# Control.net
KiCad netlist of a schematic drawn in Altium Designer
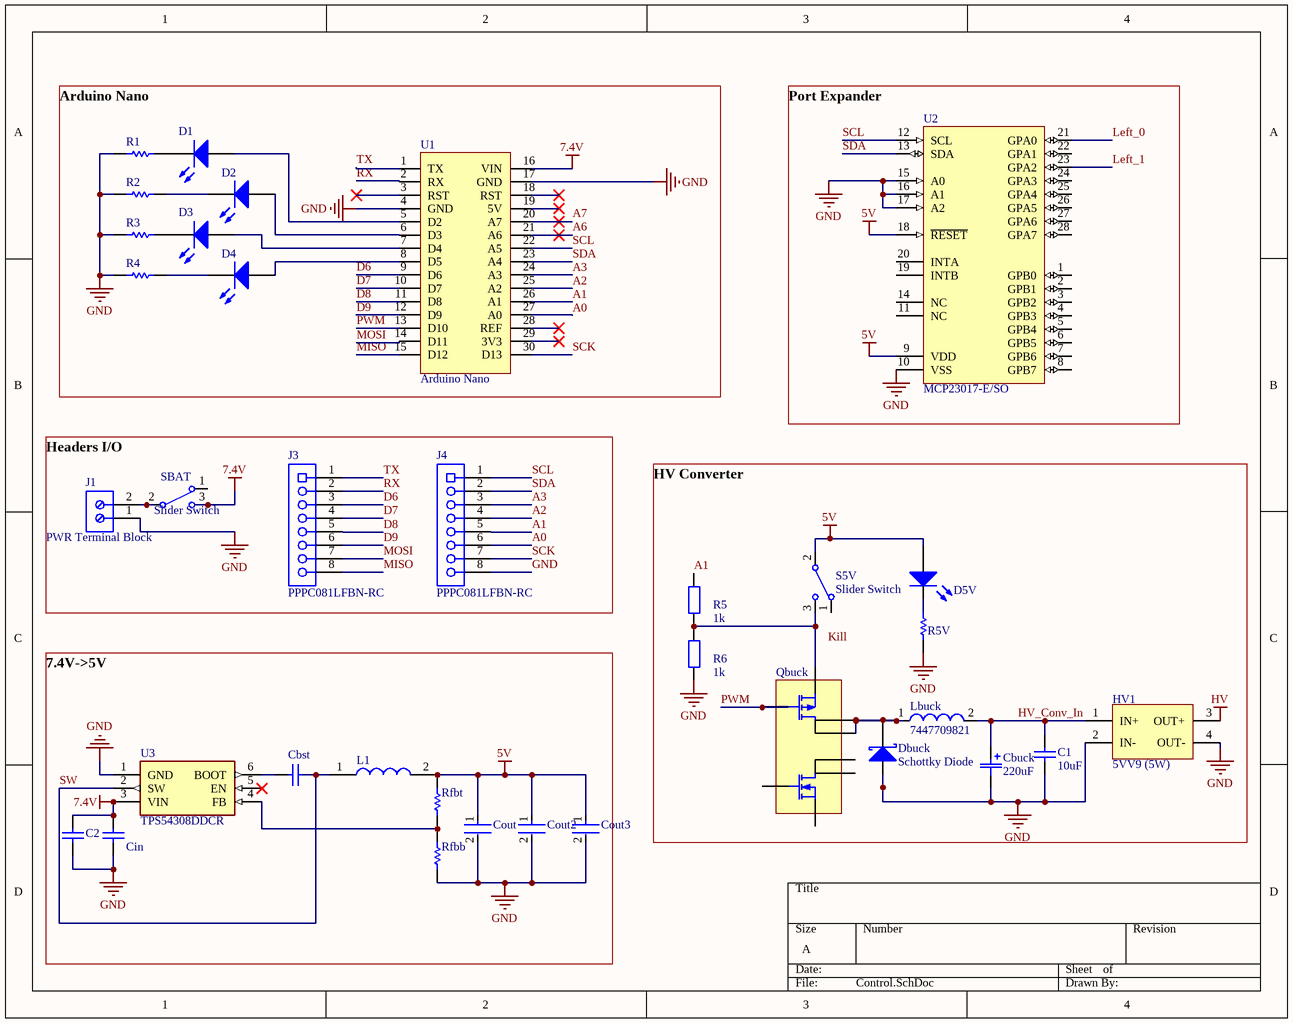
[diagram p0: Control.SchDoc]

(export (version "E")
  (design (tool "Eeschema 10.0.6"))
  (components
    (comp (ref "C1")
      (value "10uF")
      (footprint "1206 CAP")
      (description "1276-3038-6-ND\r\nManufacturer: CL31A106KAHNFNE")
      (fields (field (name "Comment") "Capacitor 10uF"))
      (libsource (lib "Schlib") (part "Capacitor 10uF"))
    )
    (comp (ref "C2")
      (value "C0805C104K5RACTU")
      (footprint "CAPC2013X88X50NL20T25")
      (fields (field (name "MANUFACTURER") "Kemet"))
      (libsource (lib "Altium Content Vault") (part "CAP"))
    )
    (comp (ref "Cbst")
      (value "CAP 100nF 50V 0805(2012)")
      (footprint "CAPC0805(2012)100_M")
      (description "CAP 100nF 50V ±20% 0805 (2012 Metric) Thickness 1mm SMD")
      (fields (field (name "TOLERANCE") "Â±20%"))
      (libsource (lib "Altium Content Vault") (part "CAP"))
    )
    (comp (ref "Cbuck")
      (value "220uF")
      (footprint "SMD 7343 - Pol")
      (description "Digikey: ‎399-8415-1-ND‎\r\nManufacturer: ‎T491X227K016AT‎")
      (fields
        (field (name "Comment") "Capacitor 220uF (Polarized)")
        (field (name "PUBLISHER") "Altium Limited")
      )
      (libsource (lib "Schlib") (part "Capacitor 220uF (Polarized)"))
    )
    (comp (ref "Cin")
      (value "GRM32ER61C226KE20L")
      (footprint "MURA-1210_H_2.7_L")
      (fields (field (name "MANUFACTURER") "Murata") (field (name "TOLERANCE") "±10%"))
      (libsource (lib "Altium Content Vault") (part "CAP-NP-2"))
    )
    (comp (ref "Cout")
      (value "CL32B106KBJNNWE")
      (footprint "FP-CL32-IPC_B")
      (description "Cap Ceramic 10uF 50V X7R ±10% SMD 1210 +125°C Embossed T/R")
      (fields (field (name "TOLERANCE") "10%"))
      (libsource (lib "Altium Content Vault") (part "b4654b650e69147ec39a6b967a45e02"))
    )
    (comp (ref "Cout2")
      (value "CL32B106KBJNNWE")
      (footprint "FP-CL32-IPC_B")
      (description "Cap Ceramic 10uF 50V X7R ±10% SMD 1210 +125°C Embossed T/R")
      (fields (field (name "TOLERANCE") "10%"))
      (libsource (lib "Altium Content Vault") (part "b4654b650e69147ec39a6b967a45e02"))
    )
    (comp (ref "Cout3")
      (value "CL32B106KBJNNWE")
      (footprint "FP-CL32-IPC_B")
      (description "Cap Ceramic 10uF 50V X7R ±10% SMD 1210 +125°C Embossed T/R")
      (fields (field (name "TOLERANCE") "10%"))
      (libsource (lib "Altium Content Vault") (part "b4654b650e69147ec39a6b967a45e02"))
    )
    (comp (ref "D1")
      (value "150080SS75000")
      (footprint "0805_A")
      (description "SMD mono-color Chip LED, WL-SMCW, Super Red")
      (fields (field (name "MANUFACTURER") "Wuerth Elektronik"))
      (libsource (lib "Altium Content Vault") (part "WE-LED_K1A2-2"))
    )
    (comp (ref "D2")
      (value "150080VS75000")
      (footprint "0805_A")
      (description "SMD mono-color Chip LED, WL-SMCW, Bright Green")
      (fields (field (name "MANUFACTURER") "Wuerth Elektronik"))
      (libsource (lib "Altium Content Vault") (part "WE-LED_K1A2-2"))
    )
    (comp (ref "D3")
      (value "150080SS75000")
      (footprint "0805_A")
      (description "SMD mono-color Chip LED, WL-SMCW, Super Red")
      (fields (field (name "MANUFACTURER") "Wuerth Elektronik"))
      (libsource (lib "Altium Content Vault") (part "WE-LED_K1A2-2"))
    )
    (comp (ref "D4")
      (value "150080VS75000")
      (footprint "0805_A")
      (description "SMD mono-color Chip LED, WL-SMCW, Bright Green")
      (fields (field (name "MANUFACTURER") "Wuerth Elektronik"))
      (libsource (lib "Altium Content Vault") (part "WE-LED_K1A2-2"))
    )
    (comp (ref "D5V")
      (value "150080VS75000")
      (footprint "0805_A")
      (description "SMD mono-color Chip LED, WL-SMCW, Bright Green")
      (fields (field (name "MANUFACTURER") "Wuerth Elektronik"))
      (libsource (lib "Altium Content Vault") (part "WE-LED_K1A2-2"))
    )
    (comp (ref "Dbuck")
      (value "Schottky Diode")
      (footprint "Schottky Diode")
      (libsource (lib "Schlib") (part "Schottky Diode"))
    )
    (comp (ref "HV1") (value "5VV9 (5W)") (footprint "5VV9") (libsource (lib "Schlib1") (part "5VV9")))
    (comp (ref "J1")
      (value "PWR Terminal Block")
      (footprint "691103110002")
      (description "Series 1031 - 3.50 mm Horizontal Entry Modular with Pressure Clamp WR-TBL, 2 pin")
      (fields
        (field (name "MANUFACTURER") "Wurth Elektronik")
        (field (name "PART NUMBER") "691103110002")
        (field (name "PUBLISHER") "WurthElektronik")
      )
      (libsource (lib "Altium Content Vault") (part "WE-CN-1P-F-TB2"))
    )
    (comp (ref "J3")
      (value "PPPC081LFBN-RC")
      (footprint "SLIN-PPPC081LFBN-RC_V")
      (libsource (lib "Altium Content Vault") (part "CN-1P-F-R8"))
    )
    (comp (ref "J4")
      (value "PPPC081LFBN-RC")
      (footprint "SLIN-PPPC081LFBN-RC_V")
      (libsource (lib "Altium Content Vault") (part "CN-1P-F-R8"))
    )
    (comp (ref "L1")
      (value "7443251600")
      (footprint "SamacSys:WE-HCI_105023")
      (description "Inductor")
      (fields (field (name "MOUSER PART NUMBER") "710-7443251600"))
      (libsource (lib "*") (part "7443251600"))
    )
    (comp (ref "Lbuck")
      (value "7447709821")
      (footprint "WE-PD-XXL")
      (description "SMD-Shielded Power Inductor WE-PD, L = 820 µH")
      (libsource (lib "Altium Content Vault") (part "PAS-IND-INDUCTOR-2"))
    )
    (comp (ref "Qbuck")
      (value "Dual MOSFET")
      (footprint "SO-8")
      (libsource (lib "Schlib") (part "Dual MOSFET"))
    )
    (comp (ref "R1")
      (value "ERJ-6GEYJ161V")
      (footprint "RESC0805(2012)_N")
      (description "160R 0.125W 5% 0805 (2012 Metric)  SMD")
      (fields (field (name "TOLERANCE") "5 %") (field (name "POWER") "0.125 W"))
      (libsource (lib "Altium Content Vault") (part "RES"))
    )
    (comp (ref "R2")
      (value "ERJ-6GEYJ161V")
      (footprint "RESC0805(2012)_N")
      (description "160R 0.125W 5% 0805 (2012 Metric)  SMD")
      (fields (field (name "TOLERANCE") "5 %") (field (name "POWER") "0.125 W"))
      (libsource (lib "Altium Content Vault") (part "RES"))
    )
    (comp (ref "R3")
      (value "ERJ-6GEYJ161V")
      (footprint "RESC0805(2012)_N")
      (description "160R 0.125W 5% 0805 (2012 Metric)  SMD")
      (fields (field (name "TOLERANCE") "5 %") (field (name "POWER") "0.125 W"))
      (libsource (lib "Altium Content Vault") (part "RES"))
    )
    (comp (ref "R4")
      (value "ERJ-6GEYJ161V")
      (footprint "RESC0805(2012)_N")
      (description "160R 0.125W 5% 0805 (2012 Metric)  SMD")
      (fields (field (name "TOLERANCE") "5 %") (field (name "POWER") "0.125 W"))
      (libsource (lib "Altium Content Vault") (part "RES"))
    )
    (comp (ref "R5")
      (value "1k")
      (footprint "1206 R")
      (description "‎541-2245-1-ND‎\r\nManufacturer: ‎RCA12061K00FKEA‎")
      (fields (field (name "Comment") "Resistor"))
      (libsource (lib "Schlib") (part "Resistor 1k"))
    )
    (comp (ref "R5V")
      (value "ERJ-6GEYJ161V")
      (footprint "RESC0805(2012)_N")
      (description "160R 0.125W 5% 0805 (2012 Metric)  SMD")
      (fields (field (name "TOLERANCE") "5 %") (field (name "POWER") "0.125 W"))
      (libsource (lib "Altium Content Vault") (part "RES"))
    )
    (comp (ref "R6")
      (value "1k")
      (footprint "1206 R")
      (description "‎541-2245-1-ND‎\r\nManufacturer: ‎RCA12061K00FKEA‎")
      (fields (field (name "Comment") "Resistor"))
      (libsource (lib "Schlib") (part "Resistor 1k"))
    )
    (comp (ref "Rfbb")
      (value "CRCW080513K7FKEA")
      (footprint "RESC2013X50X30ML20T20")
      (fields (field (name "MANUFACTURER") "Vishay Dale"))
      (libsource (lib "Altium Content Vault") (part "RES"))
    )
    (comp (ref "Rfbt")
      (value "CRCW0805100KFKEA")
      (footprint "RESC2013X50X30NL20T20")
      (fields (field (name "MANUFACTURER") "Vishay Dale"))
      (libsource (lib "Altium Content Vault") (part "RES"))
    )
    (comp (ref "S5V")
      (value "Slider Switch")
      (footprint "Slide Switch")
      (description "Digikey: ‎563-1571-ND‎\r\nManufacturer:‎ MHS122-1‎")
      (fields (field (name "PUBLISHER") "Altium Limited"))
      (libsource (lib "Schlib") (part "Switch-SPST"))
    )
    (comp (ref "SBAT")
      (value "Slider Switch")
      (footprint "Slide Switch")
      (description "Digikey: ‎563-1571-ND‎\r\nManufacturer:‎ MHS122-1‎")
      (fields (field (name "PUBLISHER") "Altium Limited"))
      (libsource (lib "Schlib") (part "Switch-SPST"))
    )
    (comp (ref "U1")
      (value "Arduino Nano")
      (footprint "Arduino Nano")
      (libsource (lib "Schlib") (part "Arduino Nano"))
    )
    (comp (ref "U2")
      (value "MCP23017-E/SO")
      (footprint "SOIC-SO28_N")
      (description "16-Bit I/O Expander with Serial Interface, 28-Pin SOIC, Extended Temperature")
      (libsource (lib "Altium Content Vault") (part "PR-BUSIC-MCP23017-28"))
    )
    (comp (ref "U3")
      (value "TPS54308DDCR")
      (footprint "SamacSys:SOT95P280X100-6N")
      (description "Power Supply")
      (fields (field (name "MOUSER PART NUMBER") "595-TPS54308DDCR"))
      (libsource (lib "*") (part "TPS54308DDCR"))
    )
  )
  (nets
    (net (code "1") (name "/A0") (class "Default")
      (node (ref "J4") (pin "6") (pinfunction "6_6") (pintype "passive"))
      (node (ref "U1") (pin "27") (pinfunction "A0_27") (pintype "passive"))
    )
    (net (code "2") (name "/A1") (class "Default")
      (node (ref "J4") (pin "5") (pinfunction "5_5") (pintype "passive"))
      (node (ref "R5") (pin "2") (pinfunction "2_2") (pintype "passive"))
      (node (ref "U1") (pin "26") (pinfunction "A1_26") (pintype "passive"))
    )
    (net (code "3") (name "/A2") (class "Default")
      (node (ref "J4") (pin "4") (pinfunction "4_4") (pintype "passive"))
      (node (ref "U1") (pin "25") (pinfunction "A2_25") (pintype "passive"))
    )
    (net (code "4") (name "/A3") (class "Default")
      (node (ref "J4") (pin "3") (pinfunction "3_3") (pintype "passive"))
      (node (ref "U1") (pin "24") (pinfunction "A3_24") (pintype "passive"))
    )
    (net (code "5") (name "/A6") (class "Default")
      (node (ref "U1") (pin "21") (pinfunction "A6_21") (pintype "passive"))
    )
    (net (code "7") (name "/A7") (class "Default")
      (node (ref "U1") (pin "20") (pinfunction "A7_20") (pintype "passive"))
    )
    (net (code "8") (name "/D6") (class "Default")
      (node (ref "J3") (pin "3") (pinfunction "3_3") (pintype "passive"))
      (node (ref "U1") (pin "9") (pinfunction "D6_9") (pintype "passive"))
    )
    (net (code "9") (name "/D7") (class "Default")
      (node (ref "J3") (pin "4") (pinfunction "4_4") (pintype "passive"))
      (node (ref "U1") (pin "10") (pinfunction "D7_10") (pintype "passive"))
    )
    (net (code "10") (name "/D8") (class "Default")
      (node (ref "J3") (pin "5") (pinfunction "5_5") (pintype "passive"))
      (node (ref "U1") (pin "11") (pinfunction "D8_11") (pintype "passive"))
    )
    (net (code "11") (name "/D9") (class "Default")
      (node (ref "J3") (pin "6") (pinfunction "6_6") (pintype "passive"))
      (node (ref "U1") (pin "12") (pinfunction "D9_12") (pintype "passive"))
    )
    (net (code "13") (name "/HV_Conv_In") (class "Default")
      (node (ref "C1") (pin "2") (pinfunction "2_2") (pintype "passive"))
      (node (ref "Cbuck") (pin "1") (pinfunction "1_1") (pintype "passive"))
      (node (ref "HV1") (pin "1") (pinfunction "IN+_1") (pintype "passive"))
      (node (ref "Lbuck") (pin "2") (pinfunction "2_2") (pintype "passive"))
    )
    (net (code "14") (name "/Left_0") (class "Default")
      (node (ref "U2") (pin "21") (pinfunction "GPA0_21") (pintype "bidirectional"))
    )
    (net (code "15") (name "/Left_1") (class "Default")
      (node (ref "U2") (pin "23") (pinfunction "GPA2_23") (pintype "bidirectional"))
    )
    (net (code "16") (name "/MISO") (class "Default")
      (node (ref "J3") (pin "8") (pinfunction "8_8") (pintype "passive"))
      (node (ref "U1") (pin "15") (pinfunction "D12_15") (pintype "passive"))
    )
    (net (code "17") (name "/MOSI") (class "Default")
      (node (ref "J3") (pin "7") (pinfunction "7_7") (pintype "passive"))
      (node (ref "U1") (pin "14") (pinfunction "D11_14") (pintype "passive"))
    )
    (net (code "18") (name "/PWM") (class "Default")
      (node (ref "Qbuck") (pin "4") (pinfunction "4_4") (pintype "passive"))
      (node (ref "U1") (pin "13") (pinfunction "D10_13") (pintype "passive"))
    )
    (net (code "19") (name "/RX") (class "Default")
      (node (ref "J3") (pin "2") (pinfunction "2_2") (pintype "passive"))
      (node (ref "U1") (pin "2") (pinfunction "RX_2") (pintype "passive"))
    )
    (net (code "20") (name "/SCK") (class "Default")
      (node (ref "J4") (pin "7") (pinfunction "7_7") (pintype "passive"))
      (node (ref "U1") (pin "30") (pinfunction "D13_30") (pintype "passive"))
    )
    (net (code "21") (name "/SCL") (class "Default")
      (node (ref "J4") (pin "1") (pinfunction "1_1") (pintype "passive"))
      (node (ref "U1") (pin "22") (pinfunction "A5_22") (pintype "passive"))
      (node (ref "U2") (pin "12") (pinfunction "SCL_12") (pintype "input"))
    )
    (net (code "22") (name "/SDA") (class "Default")
      (node (ref "J4") (pin "2") (pinfunction "2_2") (pintype "passive"))
      (node (ref "U1") (pin "23") (pinfunction "A4_23") (pintype "passive"))
      (node (ref "U2") (pin "13") (pinfunction "SDA_13") (pintype "bidirectional"))
    )
    (net (code "23") (name "/SW") (class "Default")
      (node (ref "Cbst") (pin "2") (pinfunction "2_2") (pintype "passive"))
      (node (ref "L1") (pin "1") (pinfunction "1_1") (pintype "passive"))
      (node (ref "U3") (pin "2") (pinfunction "SW_2") (pintype "output"))
    )
    (net (code "24") (name "/TX") (class "Default")
      (node (ref "J3") (pin "1") (pinfunction "1_1") (pintype "passive"))
      (node (ref "U1") (pin "1") (pinfunction "TX_1") (pintype "passive"))
    )
    (net (code "25") (name "5V") (class "Default")
      (node (ref "Cout") (pin "1") (pinfunction "1_1") (pintype "passive"))
      (node (ref "Cout2") (pin "1") (pinfunction "1_1") (pintype "passive"))
      (node (ref "Cout3") (pin "1") (pinfunction "1_1") (pintype "passive"))
      (node (ref "D5V") (pin "2") (pinfunction "A_2") (pintype "passive"))
      (node (ref "L1") (pin "2") (pinfunction "2_2") (pintype "passive"))
      (node (ref "Rfbt") (pin "2") (pinfunction "2_2") (pintype "passive"))
      (node (ref "S5V") (pin "2") (pinfunction "NO_2") (pintype "passive"))
      (node (ref "U2") (pin "18") (pinfunction "~{RESET}_18") (pintype "input"))
      (node (ref "U2") (pin "9") (pinfunction "VDD_9") (pintype "power_in"))
    )
    (net (code "26") (name "7.4V") (class "Default")
      (node (ref "C2") (pin "2") (pinfunction "2_2") (pintype "passive"))
      (node (ref "Cin") (pin "2") (pinfunction "2_2") (pintype "passive"))
      (node (ref "SBAT") (pin "3") (pinfunction "3_3") (pintype "passive"))
      (node (ref "U1") (pin "16") (pinfunction "VIN_16") (pintype "passive"))
      (node (ref "U3") (pin "3") (pinfunction "VIN_3") (pintype "power_in"))
    )
    (net (code "27") (name "GND") (class "Default")
      (node (ref "C1") (pin "1") (pinfunction "1_1") (pintype "passive"))
      (node (ref "C2") (pin "1") (pinfunction "1_1") (pintype "passive"))
      (node (ref "Cbuck") (pin "2") (pinfunction "2_2") (pintype "passive"))
      (node (ref "Cin") (pin "1") (pinfunction "1_1") (pintype "passive"))
      (node (ref "Cout") (pin "2") (pinfunction "2_2") (pintype "passive"))
      (node (ref "Cout2") (pin "2") (pinfunction "2_2") (pintype "passive"))
      (node (ref "Cout3") (pin "2") (pinfunction "2_2") (pintype "passive"))
      (node (ref "Dbuck") (pin "1") (pinfunction "A_1") (pintype "passive"))
      (node (ref "HV1") (pin "2") (pinfunction "IN-_2") (pintype "passive"))
      (node (ref "HV1") (pin "4") (pinfunction "OUT-_4") (pintype "passive"))
      (node (ref "J1") (pin "1") (pinfunction "1_1") (pintype "passive"))
      (node (ref "J4") (pin "8") (pinfunction "8_8") (pintype "passive"))
      (node (ref "R1") (pin "1") (pinfunction "1_1") (pintype "passive"))
      (node (ref "R2") (pin "1") (pinfunction "1_1") (pintype "passive"))
      (node (ref "R3") (pin "1") (pinfunction "1_1") (pintype "passive"))
      (node (ref "R4") (pin "1") (pinfunction "1_1") (pintype "passive"))
      (node (ref "R5V") (pin "1") (pinfunction "1_1") (pintype "passive"))
      (node (ref "R6") (pin "1") (pinfunction "1_1") (pintype "passive"))
      (node (ref "Rfbb") (pin "1") (pinfunction "1_1") (pintype "passive"))
      (node (ref "U1") (pin "17") (pinfunction "GND_17") (pintype "passive"))
      (node (ref "U1") (pin "4") (pinfunction "GND_4") (pintype "passive"))
      (node (ref "U2") (pin "10") (pinfunction "VSS_10") (pintype "power_in"))
      (node (ref "U2") (pin "15") (pinfunction "A0_15") (pintype "input"))
      (node (ref "U2") (pin "16") (pinfunction "A1_16") (pintype "input"))
      (node (ref "U2") (pin "17") (pinfunction "A2_17") (pintype "input"))
      (node (ref "U3") (pin "1") (pinfunction "GND_1") (pintype "power_in"))
    )
    (net (code "28") (name "HV") (class "Default")
      (node (ref "HV1") (pin "3") (pinfunction "OUT+_3") (pintype "passive"))
    )
    (net (code "29") (name "Net-(D1-A)") (class "Default")
      (node (ref "D1") (pin "2") (pinfunction "A_2") (pintype "passive"))
      (node (ref "U1") (pin "5") (pinfunction "D2_5") (pintype "passive"))
    )
    (net (code "30") (name "Net-(D1-K)") (class "Default")
      (node (ref "D1") (pin "1") (pinfunction "K_1") (pintype "passive"))
      (node (ref "R1") (pin "2") (pinfunction "2_2") (pintype "passive"))
    )
    (net (code "31") (name "Net-(D2-A)") (class "Default")
      (node (ref "D2") (pin "2") (pinfunction "A_2") (pintype "passive"))
      (node (ref "U1") (pin "6") (pinfunction "D3_6") (pintype "passive"))
    )
    (net (code "32") (name "Net-(D2-K)") (class "Default")
      (node (ref "D2") (pin "1") (pinfunction "K_1") (pintype "passive"))
      (node (ref "R2") (pin "2") (pinfunction "2_2") (pintype "passive"))
    )
    (net (code "33") (name "Net-(D3-A)") (class "Default")
      (node (ref "D3") (pin "2") (pinfunction "A_2") (pintype "passive"))
      (node (ref "U1") (pin "7") (pinfunction "D4_7") (pintype "passive"))
    )
    (net (code "34") (name "Net-(D3-K)") (class "Default")
      (node (ref "D3") (pin "1") (pinfunction "K_1") (pintype "passive"))
      (node (ref "R3") (pin "2") (pinfunction "2_2") (pintype "passive"))
    )
    (net (code "35") (name "Net-(D4-A)") (class "Default")
      (node (ref "D4") (pin "2") (pinfunction "A_2") (pintype "passive"))
      (node (ref "U1") (pin "8") (pinfunction "D5_8") (pintype "passive"))
    )
    (net (code "36") (name "Net-(D4-K)") (class "Default")
      (node (ref "D4") (pin "1") (pinfunction "K_1") (pintype "passive"))
      (node (ref "R4") (pin "2") (pinfunction "2_2") (pintype "passive"))
    )
    (net (code "37") (name "Net-(D5V-K)") (class "Default")
      (node (ref "D5V") (pin "1") (pinfunction "K_1") (pintype "passive"))
      (node (ref "R5V") (pin "2") (pinfunction "2_2") (pintype "passive"))
    )
    (net (code "38") (name "Net-(Dbuck-K)") (class "Default")
      (node (ref "Dbuck") (pin "2") (pinfunction "K_2") (pintype "passive"))
      (node (ref "Lbuck") (pin "1") (pinfunction "1_1") (pintype "passive"))
      (node (ref "Qbuck") (pin "5") (pinfunction "5_5") (pintype "passive"))
      (node (ref "Qbuck") (pin "6") (pinfunction "6_6") (pintype "passive"))
    )
    (net (code "39") (name "Net-(Qbuck-Pad3)") (class "Default")
      (node (ref "Qbuck") (pin "3") (pinfunction "3_3") (pintype "passive"))
      (node (ref "R5") (pin "1") (pinfunction "1_1") (pintype "passive"))
      (node (ref "R6") (pin "2") (pinfunction "2_2") (pintype "passive"))
      (node (ref "S5V") (pin "3") (pinfunction "3_3") (pintype "passive"))
    )
    (net (code "40") (name "Net-(SBAT-NO)") (class "Default")
      (node (ref "J1") (pin "2") (pinfunction "2_2") (pintype "passive"))
      (node (ref "SBAT") (pin "2") (pinfunction "NO_2") (pintype "passive"))
    )
    (net (code "41") (name "Net-(U3-BOOT)") (class "Default")
      (node (ref "Cbst") (pin "1") (pinfunction "1_1") (pintype "passive"))
      (node (ref "U3") (pin "6") (pinfunction "BOOT_6") (pintype "output"))
    )
    (net (code "42") (name "Net-(U3-FB)") (class "Default")
      (node (ref "Rfbb") (pin "2") (pinfunction "2_2") (pintype "passive"))
      (node (ref "Rfbt") (pin "1") (pinfunction "1_1") (pintype "passive"))
      (node (ref "U3") (pin "4") (pinfunction "FB_4") (pintype "input"))
    )
    (net (code "43") (name "unconnected-(Qbuck-Pad1)") (class "Default")
      (node (ref "Qbuck") (pin "1") (pinfunction "1_1") (pintype "passive"))
    )
    (net (code "44") (name "unconnected-(Qbuck-Pad2)") (class "Default")
      (node (ref "Qbuck") (pin "2") (pinfunction "2_2") (pintype "passive"))
    )
    (net (code "45") (name "unconnected-(Qbuck-Pad7)") (class "Default")
      (node (ref "Qbuck") (pin "7") (pinfunction "7_7") (pintype "passive"))
    )
    (net (code "46") (name "unconnected-(Qbuck-Pad8)") (class "Default")
      (node (ref "Qbuck") (pin "8") (pinfunction "8_8") (pintype "passive"))
    )
    (net (code "47") (name "unconnected-(S5V-COMMON-Pad1)") (class "Default")
      (node (ref "S5V") (pin "1") (pinfunction "COMMON_1") (pintype "passive"))
    )
    (net (code "48") (name "unconnected-(SBAT-COMMON-Pad1)") (class "Default")
      (node (ref "SBAT") (pin "1") (pinfunction "COMMON_1") (pintype "passive"))
    )
    (net (code "49") (name "unconnected-(U1-3V3-Pad29)") (class "Default")
      (node (ref "U1") (pin "29") (pinfunction "3V3_29") (pintype "passive+no_connect"))
    )
    (net (code "50") (name "unconnected-(U1-5V-Pad19)") (class "Default")
      (node (ref "U1") (pin "19") (pinfunction "5V_19") (pintype "passive+no_connect"))
    )
    (net (code "51") (name "unconnected-(U1-REF-Pad28)") (class "Default")
      (node (ref "U1") (pin "28") (pinfunction "REF_28") (pintype "passive+no_connect"))
    )
    (net (code "52") (name "unconnected-(U1-RST-Pad3)") (class "Default")
      (node (ref "U1") (pin "3") (pinfunction "RST_3") (pintype "passive+no_connect"))
    )
    (net (code "53") (name "unconnected-(U1-RST-Pad18)") (class "Default")
      (node (ref "U1") (pin "18") (pinfunction "RST_18") (pintype "passive+no_connect"))
    )
    (net (code "54") (name "unconnected-(U2-GPA1-Pad22)") (class "Default")
      (node (ref "U2") (pin "22") (pinfunction "GPA1_22") (pintype "bidirectional"))
    )
    (net (code "55") (name "unconnected-(U2-GPA3-Pad24)") (class "Default")
      (node (ref "U2") (pin "24") (pinfunction "GPA3_24") (pintype "bidirectional"))
    )
    (net (code "56") (name "unconnected-(U2-GPA4-Pad25)") (class "Default")
      (node (ref "U2") (pin "25") (pinfunction "GPA4_25") (pintype "bidirectional"))
    )
    (net (code "57") (name "unconnected-(U2-GPA5-Pad26)") (class "Default")
      (node (ref "U2") (pin "26") (pinfunction "GPA5_26") (pintype "bidirectional"))
    )
    (net (code "58") (name "unconnected-(U2-GPA6-Pad27)") (class "Default")
      (node (ref "U2") (pin "27") (pinfunction "GPA6_27") (pintype "bidirectional"))
    )
    (net (code "59") (name "unconnected-(U2-GPA7-Pad28)") (class "Default")
      (node (ref "U2") (pin "28") (pinfunction "GPA7_28") (pintype "bidirectional"))
    )
    (net (code "60") (name "unconnected-(U2-GPB0-Pad1)") (class "Default")
      (node (ref "U2") (pin "1") (pinfunction "GPB0_1") (pintype "bidirectional"))
    )
    (net (code "61") (name "unconnected-(U2-GPB1-Pad2)") (class "Default")
      (node (ref "U2") (pin "2") (pinfunction "GPB1_2") (pintype "bidirectional"))
    )
    (net (code "62") (name "unconnected-(U2-GPB2-Pad3)") (class "Default")
      (node (ref "U2") (pin "3") (pinfunction "GPB2_3") (pintype "bidirectional"))
    )
    (net (code "63") (name "unconnected-(U2-GPB3-Pad4)") (class "Default")
      (node (ref "U2") (pin "4") (pinfunction "GPB3_4") (pintype "bidirectional"))
    )
    (net (code "64") (name "unconnected-(U2-GPB4-Pad5)") (class "Default")
      (node (ref "U2") (pin "5") (pinfunction "GPB4_5") (pintype "bidirectional"))
    )
    (net (code "65") (name "unconnected-(U2-GPB5-Pad6)") (class "Default")
      (node (ref "U2") (pin "6") (pinfunction "GPB5_6") (pintype "bidirectional"))
    )
    (net (code "66") (name "unconnected-(U2-GPB6-Pad7)") (class "Default")
      (node (ref "U2") (pin "7") (pinfunction "GPB6_7") (pintype "bidirectional"))
    )
    (net (code "67") (name "unconnected-(U2-GPB7-Pad8)") (class "Default")
      (node (ref "U2") (pin "8") (pinfunction "GPB7_8") (pintype "bidirectional"))
    )
    (net (code "68") (name "unconnected-(U2-INTA-Pad20)") (class "Default")
      (node (ref "U2") (pin "20") (pinfunction "INTA_20") (pintype "open_collector"))
    )
    (net (code "69") (name "unconnected-(U2-INTB-Pad19)") (class "Default")
      (node (ref "U2") (pin "19") (pinfunction "INTB_19") (pintype "open_collector"))
    )
    (net (code "70") (name "unconnected-(U2-NC-Pad11)") (class "Default")
      (node (ref "U2") (pin "11") (pinfunction "NC_11") (pintype "passive"))
    )
    (net (code "71") (name "unconnected-(U2-NC-Pad14)") (class "Default")
      (node (ref "U2") (pin "14") (pinfunction "NC_14") (pintype "passive"))
    )
    (net (code "72") (name "unconnected-(U3-EN-Pad5)") (class "Default")
      (node (ref "U3") (pin "5") (pinfunction "EN_5") (pintype "input+no_connect"))
    )
  )
)
